# solenoid_valve.net
KiCad netlist of a schematic drawn in EAGLE
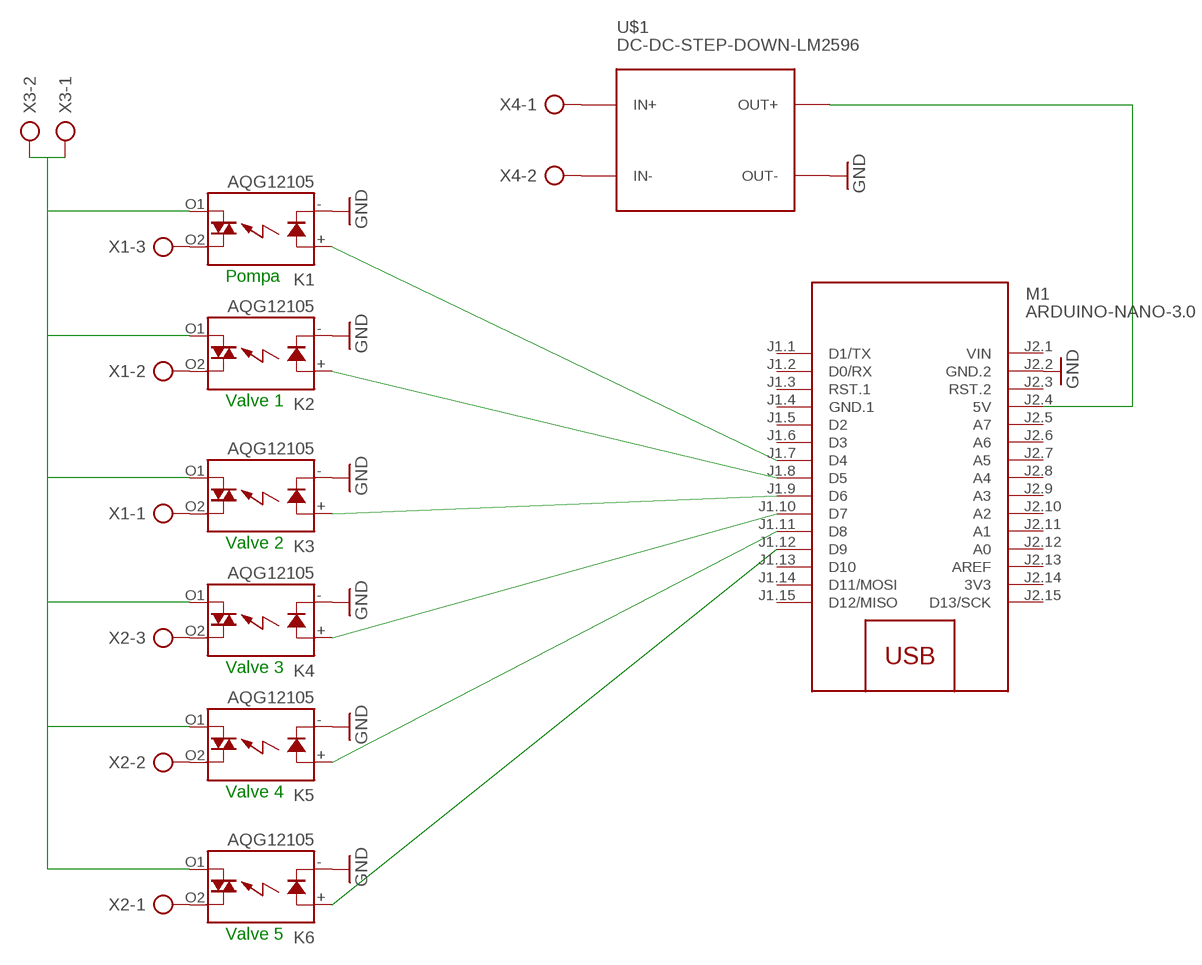
[diagram p0: schematic, sheet 1]

(export (version "E")
  (design (tool "Eeschema 10.0.6"))
  (components
    (comp (ref "K1")
      (value "AQG12105")
      (footprint "eagle-import:AQG")
      (fields (field (name "MF") "AROMAT/ MATSUSHITA"))
      (libsource (lib "eagle-import") (part "AQG12105"))
    )
    (comp (ref "K2")
      (value "AQG12105")
      (footprint "eagle-import:AQG")
      (fields (field (name "MF") "AROMAT/ MATSUSHITA"))
      (libsource (lib "eagle-import") (part "AQG12105"))
    )
    (comp (ref "K3")
      (value "AQG12105")
      (footprint "eagle-import:AQG")
      (fields (field (name "MF") "AROMAT/ MATSUSHITA"))
      (libsource (lib "eagle-import") (part "AQG12105"))
    )
    (comp (ref "K4")
      (value "AQG12105")
      (footprint "eagle-import:AQG")
      (fields (field (name "MF") "AROMAT/ MATSUSHITA"))
      (libsource (lib "eagle-import") (part "AQG12105"))
    )
    (comp (ref "K5")
      (value "AQG12105")
      (footprint "eagle-import:AQG")
      (fields (field (name "MF") "AROMAT/ MATSUSHITA"))
      (libsource (lib "eagle-import") (part "AQG12105"))
    )
    (comp (ref "K6")
      (value "AQG12105")
      (footprint "eagle-import:AQG")
      (fields (field (name "MF") "AROMAT/ MATSUSHITA"))
      (libsource (lib "eagle-import") (part "AQG12105"))
    )
    (comp (ref "M1")
      (value "ARDUINO-NANO-3.0")
      (footprint "eagle-import:ARDUINO-NANO-3.0")
      (libsource (lib "eagle-import") (part "ARDUINO-NANO-3.0"))
    )
    (comp (ref "U$1")
      (value "DC-DC-STEP-DOWN-LM2596")
      (footprint "eagle-import:DC-DC-STEP-DOWN-LM2596")
      (libsource (lib "eagle-import") (part "DC-DC-STEP-DOWN-LM2596"))
    )
    (comp (ref "X1")
      (value "AK300/3")
      (footprint "eagle-import:AK300_3")
      (libsource (lib "eagle-import") (part "AK300/3"))
    )
    (comp (ref "X2")
      (value "AK300/3")
      (footprint "eagle-import:AK300_3")
      (libsource (lib "eagle-import") (part "AK300/3"))
    )
    (comp (ref "X3")
      (value "AK300/2")
      (footprint "eagle-import:AK300_2")
      (libsource (lib "eagle-import") (part "AK300/2"))
    )
    (comp (ref "X4")
      (value "AK300/2")
      (footprint "eagle-import:AK300_2")
      (libsource (lib "eagle-import") (part "AK300/2"))
    )
  )
  (nets
    (net (code "1") (name "/3V3") (class "Default")
      (node (ref "M1") (pin "J2.14") (pinfunction "3V3_J2.14") (pintype "power_in"))
    )
    (net (code "2") (name "/GND.1") (class "Default")
      (node (ref "M1") (pin "J1.4") (pinfunction "GND.1_J1.4") (pintype "power_in"))
    )
    (net (code "3") (name "/VIN") (class "Default")
      (node (ref "M1") (pin "J2.1") (pinfunction "VIN_J2.1") (pintype "power_in"))
    )
    (net (code "4") (name "GND") (class "Default")
      (node (ref "K1") (pin "-") (pinfunction "K_-") (pintype "passive"))
      (node (ref "K2") (pin "-") (pinfunction "K_-") (pintype "passive"))
      (node (ref "K3") (pin "-") (pinfunction "K_-") (pintype "passive"))
      (node (ref "K4") (pin "-") (pinfunction "K_-") (pintype "passive"))
      (node (ref "K5") (pin "-") (pinfunction "K_-") (pintype "passive"))
      (node (ref "K6") (pin "-") (pinfunction "K_-") (pintype "passive"))
      (node (ref "M1") (pin "J2.2") (pinfunction "GND.2_J2.2") (pintype "power_in"))
      (node (ref "U$1") (pin "OUT-") (pinfunction "OUT-_OUT-") (pintype "bidirectional"))
    )
    (net (code "5") (name "Net-(K1-A)") (class "Default")
      (node (ref "K1") (pin "+") (pinfunction "A_+") (pintype "passive"))
      (node (ref "M1") (pin "J1.7") (pinfunction "D4_J1.7") (pintype "bidirectional"))
    )
    (net (code "6") (name "Net-(K1-DS1)") (class "Default")
      (node (ref "K1") (pin "O2") (pinfunction "DS1_O2") (pintype "passive"))
      (node (ref "X1") (pin "3") (pinfunction "KL_3") (pintype "passive"))
    )
    (net (code "7") (name "Net-(K1-DS2)") (class "Default")
      (node (ref "K1") (pin "O1") (pinfunction "DS2_O1") (pintype "passive"))
      (node (ref "K2") (pin "O1") (pinfunction "DS2_O1") (pintype "passive"))
      (node (ref "K3") (pin "O1") (pinfunction "DS2_O1") (pintype "passive"))
      (node (ref "K4") (pin "O1") (pinfunction "DS2_O1") (pintype "passive"))
      (node (ref "K5") (pin "O1") (pinfunction "DS2_O1") (pintype "passive"))
      (node (ref "K6") (pin "O1") (pinfunction "DS2_O1") (pintype "passive"))
      (node (ref "X3") (pin "1") (pinfunction "KL_1") (pintype "passive"))
      (node (ref "X3") (pin "2") (pinfunction "KL_2") (pintype "passive"))
    )
    (net (code "8") (name "Net-(K2-A)") (class "Default")
      (node (ref "K2") (pin "+") (pinfunction "A_+") (pintype "passive"))
      (node (ref "M1") (pin "J1.8") (pinfunction "D5_J1.8") (pintype "bidirectional"))
    )
    (net (code "9") (name "Net-(K2-DS1)") (class "Default")
      (node (ref "K2") (pin "O2") (pinfunction "DS1_O2") (pintype "passive"))
      (node (ref "X1") (pin "2") (pinfunction "KL_2") (pintype "passive"))
    )
    (net (code "10") (name "Net-(K3-A)") (class "Default")
      (node (ref "K3") (pin "+") (pinfunction "A_+") (pintype "passive"))
      (node (ref "M1") (pin "J1.9") (pinfunction "D6_J1.9") (pintype "bidirectional"))
    )
    (net (code "11") (name "Net-(K3-DS1)") (class "Default")
      (node (ref "K3") (pin "O2") (pinfunction "DS1_O2") (pintype "passive"))
      (node (ref "X1") (pin "1") (pinfunction "KL_1") (pintype "passive"))
    )
    (net (code "12") (name "Net-(K4-A)") (class "Default")
      (node (ref "K4") (pin "+") (pinfunction "A_+") (pintype "passive"))
      (node (ref "M1") (pin "J1.10") (pinfunction "D7_J1.10") (pintype "bidirectional"))
    )
    (net (code "13") (name "Net-(K4-DS1)") (class "Default")
      (node (ref "K4") (pin "O2") (pinfunction "DS1_O2") (pintype "passive"))
      (node (ref "X2") (pin "3") (pinfunction "KL_3") (pintype "passive"))
    )
    (net (code "14") (name "Net-(K5-A)") (class "Default")
      (node (ref "K5") (pin "+") (pinfunction "A_+") (pintype "passive"))
      (node (ref "M1") (pin "J1.11") (pinfunction "D8_J1.11") (pintype "bidirectional"))
    )
    (net (code "15") (name "Net-(K5-DS1)") (class "Default")
      (node (ref "K5") (pin "O2") (pinfunction "DS1_O2") (pintype "passive"))
      (node (ref "X2") (pin "2") (pinfunction "KL_2") (pintype "passive"))
    )
    (net (code "16") (name "Net-(K6-A)") (class "Default")
      (node (ref "K6") (pin "+") (pinfunction "A_+") (pintype "passive"))
      (node (ref "M1") (pin "J1.12") (pinfunction "D9_J1.12") (pintype "bidirectional"))
    )
    (net (code "17") (name "Net-(K6-DS1)") (class "Default")
      (node (ref "K6") (pin "O2") (pinfunction "DS1_O2") (pintype "passive"))
      (node (ref "X2") (pin "1") (pinfunction "KL_1") (pintype "passive"))
    )
    (net (code "18") (name "Net-(M1-5V)") (class "Default")
      (node (ref "M1") (pin "J2.4") (pinfunction "5V_J2.4") (pintype "power_in"))
      (node (ref "U$1") (pin "OUT+") (pinfunction "OUT+_OUT+") (pintype "bidirectional"))
    )
    (net (code "19") (name "Net-(X4A-KL)") (class "Default")
      (node (ref "U$1") (pin "IN+") (pinfunction "IN+_IN+") (pintype "bidirectional"))
      (node (ref "X4") (pin "1") (pinfunction "KL_1") (pintype "passive"))
    )
    (net (code "20") (name "Net-(X4B-KL)") (class "Default")
      (node (ref "U$1") (pin "IN-") (pinfunction "IN-_IN-") (pintype "bidirectional"))
      (node (ref "X4") (pin "2") (pinfunction "KL_2") (pintype "passive"))
    )
    (net (code "21") (name "unconnected-(M1-A0-PadJ2.12)") (class "Default")
      (node (ref "M1") (pin "J2.12") (pinfunction "A0_J2.12") (pintype "bidirectional"))
    )
    (net (code "22") (name "unconnected-(M1-A1-PadJ2.11)") (class "Default")
      (node (ref "M1") (pin "J2.11") (pinfunction "A1_J2.11") (pintype "bidirectional"))
    )
    (net (code "23") (name "unconnected-(M1-A2-PadJ2.10)") (class "Default")
      (node (ref "M1") (pin "J2.10") (pinfunction "A2_J2.10") (pintype "bidirectional"))
    )
    (net (code "24") (name "unconnected-(M1-A3-PadJ2.9)") (class "Default")
      (node (ref "M1") (pin "J2.9") (pinfunction "A3_J2.9") (pintype "bidirectional"))
    )
    (net (code "25") (name "unconnected-(M1-A4-PadJ2.8)") (class "Default")
      (node (ref "M1") (pin "J2.8") (pinfunction "A4_J2.8") (pintype "bidirectional"))
    )
    (net (code "26") (name "unconnected-(M1-A5-PadJ2.7)") (class "Default")
      (node (ref "M1") (pin "J2.7") (pinfunction "A5_J2.7") (pintype "bidirectional"))
    )
    (net (code "27") (name "unconnected-(M1-A6-PadJ2.6)") (class "Default")
      (node (ref "M1") (pin "J2.6") (pinfunction "A6_J2.6") (pintype "bidirectional"))
    )
    (net (code "28") (name "unconnected-(M1-A7-PadJ2.5)") (class "Default")
      (node (ref "M1") (pin "J2.5") (pinfunction "A7_J2.5") (pintype "bidirectional"))
    )
    (net (code "29") (name "unconnected-(M1-AREF-PadJ2.13)") (class "Default")
      (node (ref "M1") (pin "J2.13") (pinfunction "AREF_J2.13") (pintype "bidirectional"))
    )
    (net (code "30") (name "unconnected-(M1-D0{slash}RX-PadJ1.2)") (class "Default")
      (node (ref "M1") (pin "J1.2") (pinfunction "D0/RX_J1.2") (pintype "bidirectional"))
    )
    (net (code "31") (name "unconnected-(M1-D1{slash}TX-PadJ1.1)") (class "Default")
      (node (ref "M1") (pin "J1.1") (pinfunction "D1/TX_J1.1") (pintype "bidirectional"))
    )
    (net (code "32") (name "unconnected-(M1-D2-PadJ1.5)") (class "Default")
      (node (ref "M1") (pin "J1.5") (pinfunction "D2_J1.5") (pintype "bidirectional"))
    )
    (net (code "33") (name "unconnected-(M1-D3-PadJ1.6)") (class "Default")
      (node (ref "M1") (pin "J1.6") (pinfunction "D3_J1.6") (pintype "bidirectional"))
    )
    (net (code "34") (name "unconnected-(M1-D10-PadJ1.13)") (class "Default")
      (node (ref "M1") (pin "J1.13") (pinfunction "D10_J1.13") (pintype "bidirectional"))
    )
    (net (code "35") (name "unconnected-(M1-D11{slash}MOSI-PadJ1.14)") (class "Default")
      (node (ref "M1") (pin "J1.14") (pinfunction "D11/MOSI_J1.14") (pintype "bidirectional"))
    )
    (net (code "36") (name "unconnected-(M1-D12{slash}MISO-PadJ1.15)") (class "Default")
      (node (ref "M1") (pin "J1.15") (pinfunction "D12/MISO_J1.15") (pintype "bidirectional"))
    )
    (net (code "37") (name "unconnected-(M1-D13{slash}SCK-PadJ2.15)") (class "Default")
      (node (ref "M1") (pin "J2.15") (pinfunction "D13/SCK_J2.15") (pintype "bidirectional"))
    )
    (net (code "38") (name "unconnected-(M1-RST.1-PadJ1.3)") (class "Default")
      (node (ref "M1") (pin "J1.3") (pinfunction "RST.1_J1.3") (pintype "bidirectional"))
    )
    (net (code "39") (name "unconnected-(M1-RST.2-PadJ2.3)") (class "Default")
      (node (ref "M1") (pin "J2.3") (pinfunction "RST.2_J2.3") (pintype "bidirectional"))
    )
  )
)
